# Ringer.net
KiCad netlist of a schematic drawn in EAGLE
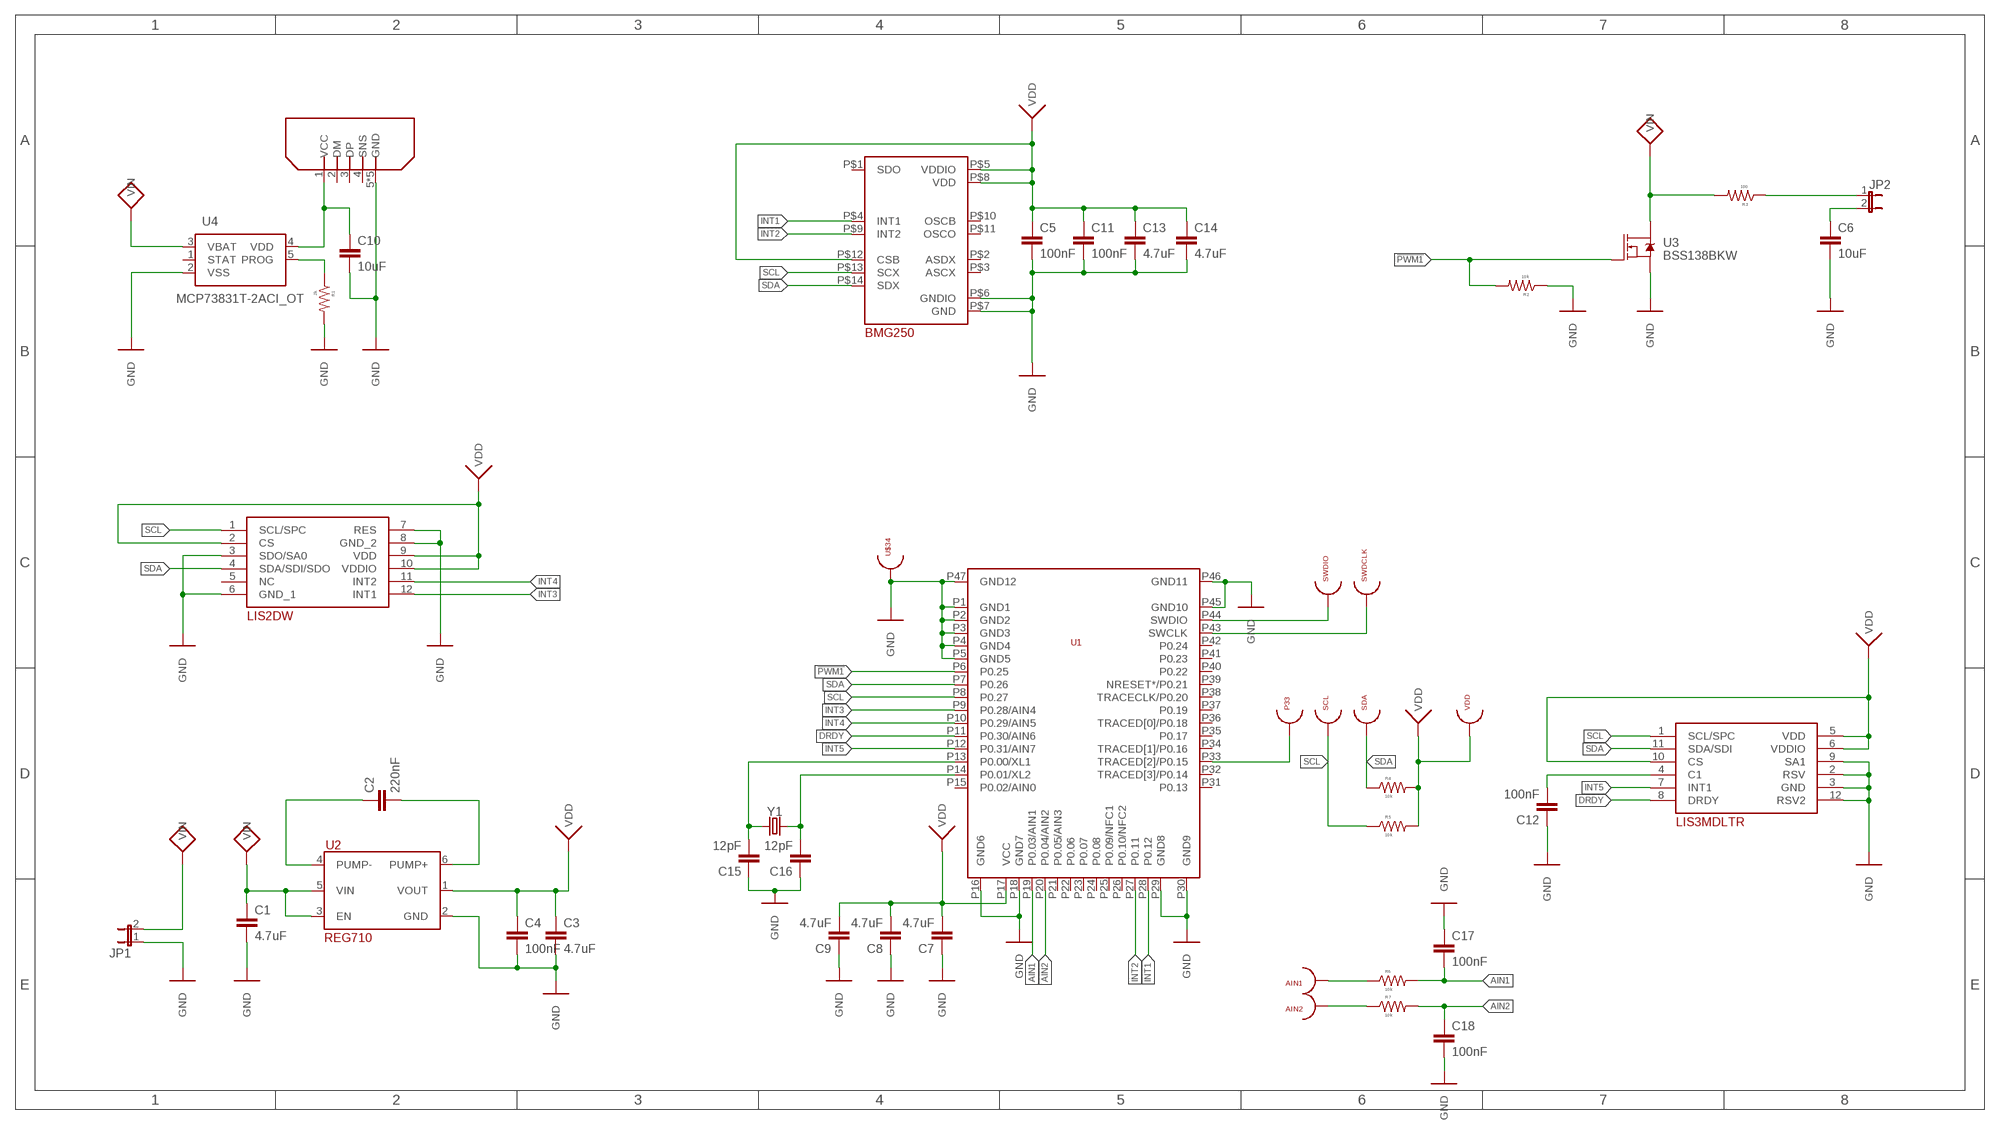
[diagram p0: schematic, sheet 1]

(export (version "E")
  (design (tool "Eeschema 10.0.6"))
  (components
    (comp (ref "AIN1")
      (value "TESTPOINT_22")
      (footprint "eagle-import:TESTPOINT_22")
      (libsource (lib "eagle-import") (part "TESTPOINT_22"))
    )
    (comp (ref "AIN2")
      (value "TESTPOINT_22")
      (footprint "eagle-import:TESTPOINT_22")
      (libsource (lib "eagle-import") (part "TESTPOINT_22"))
    )
    (comp (ref "C1")
      (value "4.7uF")
      (footprint "eagle-import:C0603")
      (libsource (lib "eagle-import") (part "CAPACITOR0603"))
    )
    (comp (ref "C2")
      (value "220nF")
      (footprint "eagle-import:C0603")
      (libsource (lib "eagle-import") (part "CAPACITOR0603"))
    )
    (comp (ref "C3")
      (value "4.7uF")
      (footprint "eagle-import:C0603")
      (libsource (lib "eagle-import") (part "CAPACITOR0603"))
    )
    (comp (ref "C4")
      (value "100nF")
      (footprint "eagle-import:C0603")
      (libsource (lib "eagle-import") (part "CAPACITOR0603"))
    )
    (comp (ref "C5")
      (value "100nF")
      (footprint "eagle-import:C0603")
      (libsource (lib "eagle-import") (part "CAPACITOR0603"))
    )
    (comp (ref "C6")
      (value "10uF")
      (footprint "eagle-import:C0805")
      (libsource (lib "eagle-import") (part "CAPACITOR0805"))
    )
    (comp (ref "C7")
      (value "4.7uF")
      (footprint "eagle-import:C0603")
      (libsource (lib "eagle-import") (part "CAPACITOR0603"))
    )
    (comp (ref "C8")
      (value "4.7uF")
      (footprint "eagle-import:C0603")
      (libsource (lib "eagle-import") (part "CAPACITOR0603"))
    )
    (comp (ref "C9")
      (value "4.7uF")
      (footprint "eagle-import:C0603")
      (libsource (lib "eagle-import") (part "CAPACITOR0603"))
    )
    (comp (ref "C10")
      (value "10uF")
      (footprint "eagle-import:C0603")
      (libsource (lib "eagle-import") (part "CAPACITOR0603"))
    )
    (comp (ref "C11")
      (value "100nF")
      (footprint "eagle-import:C0603")
      (libsource (lib "eagle-import") (part "CAPACITOR0603"))
    )
    (comp (ref "C12")
      (value "100nF")
      (footprint "eagle-import:C0603")
      (libsource (lib "eagle-import") (part "CAPACITOR0603"))
    )
    (comp (ref "C13")
      (value "4.7uF")
      (footprint "eagle-import:C0603")
      (libsource (lib "eagle-import") (part "CAPACITOR0603"))
    )
    (comp (ref "C14")
      (value "4.7uF")
      (footprint "eagle-import:C0603")
      (libsource (lib "eagle-import") (part "CAPACITOR0603"))
    )
    (comp (ref "C15")
      (value "12pF")
      (footprint "eagle-import:C0603")
      (libsource (lib "eagle-import") (part "CAPACITOR0603"))
    )
    (comp (ref "C16")
      (value "12pF")
      (footprint "eagle-import:C0603")
      (libsource (lib "eagle-import") (part "CAPACITOR0603"))
    )
    (comp (ref "C17")
      (value "100nF")
      (footprint "eagle-import:C0603")
      (libsource (lib "eagle-import") (part "CAPACITOR0603"))
    )
    (comp (ref "C18")
      (value "100nF")
      (footprint "eagle-import:C0603")
      (libsource (lib "eagle-import") (part "CAPACITOR0603"))
    )
    (comp (ref "IC1")
      (value "LIS2DW12TR")
      (footprint "eagle-import:LGA-12")
      (fields (field (name "MOUSER_PART_NUMBER") "511-LIS2DW12TR"))
      (libsource (lib "eagle-import") (part "LIS2DW12TR"))
    )
    (comp (ref "JP1")
      (value "JP1E")
      (footprint "eagle-import:JP1")
      (libsource (lib "eagle-import") (part "JP1E"))
    )
    (comp (ref "JP2")
      (value "JP1E")
      (footprint "eagle-import:JP1")
      (libsource (lib "eagle-import") (part "JP1E"))
    )
    (comp (ref "P33")
      (value "TESTPOINT_22")
      (footprint "eagle-import:TESTPOINT_22")
      (libsource (lib "eagle-import") (part "TESTPOINT_22"))
    )
    (comp (ref "R1")
      (value "2k")
      (footprint "eagle-import:R0603")
      (libsource (lib "eagle-import") (part "RESISTOR0603"))
    )
    (comp (ref "R2")
      (value "10k")
      (footprint "eagle-import:R0603")
      (libsource (lib "eagle-import") (part "RESISTOR0603"))
    )
    (comp (ref "R3")
      (value "100")
      (footprint "eagle-import:R0805")
      (libsource (lib "eagle-import") (part "RESISTOR0805"))
    )
    (comp (ref "R4")
      (value "10k")
      (footprint "eagle-import:R0603")
      (libsource (lib "eagle-import") (part "RESISTOR0603"))
    )
    (comp (ref "R5")
      (value "10k")
      (footprint "eagle-import:R0603")
      (libsource (lib "eagle-import") (part "RESISTOR0603"))
    )
    (comp (ref "R6")
      (value "10k")
      (footprint "eagle-import:R0603")
      (libsource (lib "eagle-import") (part "RESISTOR0603"))
    )
    (comp (ref "R7")
      (value "10k")
      (footprint "eagle-import:R0603")
      (libsource (lib "eagle-import") (part "RESISTOR0603"))
    )
    (comp (ref "SCL")
      (value "TESTPOINT_22")
      (footprint "eagle-import:TESTPOINT_22")
      (libsource (lib "eagle-import") (part "TESTPOINT_22"))
    )
    (comp (ref "SDA")
      (value "TESTPOINT_22")
      (footprint "eagle-import:TESTPOINT_22")
      (libsource (lib "eagle-import") (part "TESTPOINT_22"))
    )
    (comp (ref "SWDCLK")
      (value "TESTPOINT_22")
      (footprint "eagle-import:TESTPOINT_22")
      (libsource (lib "eagle-import") (part "TESTPOINT_22"))
    )
    (comp (ref "SWDIO")
      (value "TESTPOINT_22")
      (footprint "eagle-import:TESTPOINT_22")
      (libsource (lib "eagle-import") (part "TESTPOINT_22"))
    )
    (comp (ref "U$23")
      (value "ZX80B5P")
      (footprint "eagle-import:ZX80B5P")
      (libsource (lib "eagle-import") (part "ZX80B5P"))
    )
    (comp (ref "U$29")
      (value "LIS3MDLTR")
      (footprint "eagle-import:LGA-12")
      (libsource (lib "eagle-import") (part "LIS3MDLTR"))
    )
    (comp (ref "U$34")
      (value "TESTPOINT_22")
      (footprint "eagle-import:TESTPOINT_22")
      (libsource (lib "eagle-import") (part "TESTPOINT_22"))
    )
    (comp (ref "U1")
      (value "BMD-300")
      (footprint "eagle-import:BMD-300")
      (libsource (lib "eagle-import") (part "BMD-300"))
    )
    (comp (ref "U2")
      (value "REG710")
      (footprint "eagle-import:SOT457")
      (libsource (lib "eagle-import") (part "REG710"))
    )
    (comp (ref "U3")
      (value "BSS138BKW")
      (footprint "eagle-import:SOT65P210X110-3N")
      (libsource (lib "eagle-import") (part "BSS138BKW"))
    )
    (comp (ref "U4")
      (value "MCP73831T-2ACI_OT")
      (footprint "eagle-import:SOT95P270X145-5N")
      (fields
        (field (name "MANUFACTURER_PART_NUMBER") "MCP73831T-2ACI/OT")
        (field (name "MOUSER_PART_NUMBER") "579-MCP73831T-2ACIOT")
      )
      (libsource (lib "eagle-import") (part "MCP73831T-2ACI_OT"))
    )
    (comp (ref "U5")
      (value "BMG250")
      (footprint "eagle-import:LGA14")
      (libsource (lib "eagle-import") (part "BMG250"))
    )
    (comp (ref "VDD")
      (value "TESTPOINT_22")
      (footprint "eagle-import:TESTPOINT_22")
      (libsource (lib "eagle-import") (part "TESTPOINT_22"))
    )
    (comp (ref "Y1")
      (value "CRYSTALSMD-3.2X1.5")
      (footprint "eagle-import:CRYSTAL-SMD-3.2X1.5MM")
      (libsource (lib "eagle-import") (part "CRYSTALSMD-3.2X1.5"))
    )
  )
  (nets
    (net (code "1") (name "/~{PWM1}") (class "Default")
      (node (ref "R2") (pin "2") (pinfunction "2_2") (pintype "passive"))
      (node (ref "U1") (pin "P6") (pinfunction "P0.25_P6") (pintype "bidirectional"))
      (node (ref "U3") (pin "1") (pinfunction "G_1") (pintype "bidirectional"))
    )
    (net (code "2") (name "AIN1") (class "Default")
      (node (ref "C17") (pin "2") (pinfunction "2_2") (pintype "passive"))
      (node (ref "R6") (pin "2") (pinfunction "2_2") (pintype "passive"))
      (node (ref "U1") (pin "P19") (pinfunction "P0.03/AIN1_P19") (pintype "bidirectional"))
    )
    (net (code "3") (name "AIN2") (class "Default")
      (node (ref "C18") (pin "1") (pinfunction "1_1") (pintype "passive"))
      (node (ref "R7") (pin "2") (pinfunction "2_2") (pintype "passive"))
      (node (ref "U1") (pin "P20") (pinfunction "P0.04/AIN2_P20") (pintype "bidirectional"))
    )
    (net (code "4") (name "DRDY") (class "Default")
      (node (ref "U$29") (pin "8") (pinfunction "DRDY_8") (pintype "bidirectional"))
      (node (ref "U1") (pin "P11") (pinfunction "P0.30/AIN6_P11") (pintype "bidirectional"))
    )
    (net (code "5") (name "GND") (class "Default")
      (node (ref "C1") (pin "2") (pinfunction "2_2") (pintype "passive"))
      (node (ref "C10") (pin "2") (pinfunction "2_2") (pintype "passive"))
      (node (ref "C11") (pin "2") (pinfunction "2_2") (pintype "passive"))
      (node (ref "C12") (pin "1") (pinfunction "1_1") (pintype "passive"))
      (node (ref "C13") (pin "2") (pinfunction "2_2") (pintype "passive"))
      (node (ref "C14") (pin "2") (pinfunction "2_2") (pintype "passive"))
      (node (ref "C15") (pin "1") (pinfunction "1_1") (pintype "passive"))
      (node (ref "C16") (pin "1") (pinfunction "1_1") (pintype "passive"))
      (node (ref "C17") (pin "1") (pinfunction "1_1") (pintype "passive"))
      (node (ref "C18") (pin "2") (pinfunction "2_2") (pintype "passive"))
      (node (ref "C3") (pin "2") (pinfunction "2_2") (pintype "passive"))
      (node (ref "C4") (pin "2") (pinfunction "2_2") (pintype "passive"))
      (node (ref "C5") (pin "2") (pinfunction "2_2") (pintype "passive"))
      (node (ref "C6") (pin "2") (pinfunction "2_2") (pintype "passive"))
      (node (ref "C7") (pin "1") (pinfunction "1_1") (pintype "passive"))
      (node (ref "C8") (pin "1") (pinfunction "1_1") (pintype "passive"))
      (node (ref "C9") (pin "1") (pinfunction "1_1") (pintype "passive"))
      (node (ref "IC1") (pin "3") (pinfunction "SDO/SA0_3") (pintype "bidirectional"))
      (node (ref "IC1") (pin "6") (pinfunction "GND_1_6") (pintype "bidirectional"))
      (node (ref "IC1") (pin "7") (pinfunction "RES_7") (pintype "bidirectional"))
      (node (ref "IC1") (pin "8") (pinfunction "GND_2_8") (pintype "bidirectional"))
      (node (ref "JP1") (pin "1") (pinfunction "1_1") (pintype "passive"))
      (node (ref "R1") (pin "2") (pinfunction "2_2") (pintype "passive"))
      (node (ref "R2") (pin "1") (pinfunction "1_1") (pintype "passive"))
      (node (ref "U$23") (pin "5") (pinfunction "GND_5") (pintype "bidirectional"))
      (node (ref "U$23") (pin "GND1") (pinfunction "GND_GND1") (pintype "bidirectional"))
      (node (ref "U$23") (pin "GND2") (pinfunction "GND_GND2") (pintype "bidirectional"))
      (node (ref "U$23") (pin "GND3") (pinfunction "GND_GND3") (pintype "bidirectional"))
      (node (ref "U$23") (pin "GND4") (pinfunction "GND_GND4") (pintype "bidirectional"))
      (node (ref "U$29") (pin "12") (pinfunction "RSV2_12") (pintype "bidirectional"))
      (node (ref "U$29") (pin "2") (pinfunction "RSV_2") (pintype "bidirectional"))
      (node (ref "U$29") (pin "3") (pinfunction "GND_3") (pintype "bidirectional"))
      (node (ref "U$29") (pin "9") (pinfunction "SA1_9") (pintype "bidirectional"))
      (node (ref "U$34") (pin "P$1") (pinfunction "P$1_P$1") (pintype "bidirectional"))
      (node (ref "U1") (pin "P1") (pinfunction "GND1_P1") (pintype "bidirectional"))
      (node (ref "U1") (pin "P16") (pinfunction "GND6_P16") (pintype "bidirectional"))
      (node (ref "U1") (pin "P18") (pinfunction "GND7_P18") (pintype "bidirectional"))
      (node (ref "U1") (pin "P2") (pinfunction "GND2_P2") (pintype "bidirectional"))
      (node (ref "U1") (pin "P29") (pinfunction "GND8_P29") (pintype "bidirectional"))
      (node (ref "U1") (pin "P3") (pinfunction "GND3_P3") (pintype "bidirectional"))
      (node (ref "U1") (pin "P30") (pinfunction "GND9_P30") (pintype "bidirectional"))
      (node (ref "U1") (pin "P4") (pinfunction "GND4_P4") (pintype "bidirectional"))
      (node (ref "U1") (pin "P45") (pinfunction "GND10_P45") (pintype "bidirectional"))
      (node (ref "U1") (pin "P46") (pinfunction "GND11_P46") (pintype "bidirectional"))
      (node (ref "U1") (pin "P47") (pinfunction "GND12_P47") (pintype "bidirectional"))
      (node (ref "U1") (pin "P5") (pinfunction "GND5_P5") (pintype "bidirectional"))
      (node (ref "U2") (pin "2") (pinfunction "GND_2") (pintype "bidirectional"))
      (node (ref "U3") (pin "2") (pinfunction "S_2") (pintype "bidirectional"))
      (node (ref "U4") (pin "2") (pinfunction "VSS_2") (pintype "bidirectional"))
      (node (ref "U5") (pin "P$6") (pinfunction "GNDIO_P$6") (pintype "power_in"))
      (node (ref "U5") (pin "P$7") (pinfunction "GND_P$7") (pintype "power_in"))
    )
    (net (code "6") (name "INT1") (class "Default")
      (node (ref "U1") (pin "P28") (pinfunction "P0.12_P28") (pintype "bidirectional"))
      (node (ref "U5") (pin "P$4") (pinfunction "INT1_P$4") (pintype "bidirectional"))
    )
    (net (code "7") (name "INT2") (class "Default")
      (node (ref "U1") (pin "P27") (pinfunction "P0.11_P27") (pintype "bidirectional"))
      (node (ref "U5") (pin "P$9") (pinfunction "INT2_P$9") (pintype "bidirectional"))
    )
    (net (code "8") (name "INT3") (class "Default")
      (node (ref "IC1") (pin "12") (pinfunction "INT1_12") (pintype "bidirectional"))
      (node (ref "U1") (pin "P9") (pinfunction "P0.28/AIN4_P9") (pintype "bidirectional"))
    )
    (net (code "9") (name "INT4") (class "Default")
      (node (ref "IC1") (pin "11") (pinfunction "INT2_11") (pintype "bidirectional"))
      (node (ref "U1") (pin "P10") (pinfunction "P0.29/AIN5_P10") (pintype "bidirectional"))
    )
    (net (code "10") (name "INT5") (class "Default")
      (node (ref "U$29") (pin "7") (pinfunction "INT1_7") (pintype "bidirectional"))
      (node (ref "U1") (pin "P12") (pinfunction "P0.31/AIN7_P12") (pintype "bidirectional"))
    )
    (net (code "11") (name "Net-(AIN1-PadP$1)") (class "Default")
      (node (ref "AIN1") (pin "P$1") (pinfunction "P$1_P$1") (pintype "bidirectional"))
      (node (ref "R6") (pin "1") (pinfunction "1_1") (pintype "passive"))
    )
    (net (code "12") (name "Net-(AIN2-PadP$1)") (class "Default")
      (node (ref "AIN2") (pin "P$1") (pinfunction "P$1_P$1") (pintype "bidirectional"))
      (node (ref "R7") (pin "1") (pinfunction "1_1") (pintype "passive"))
    )
    (net (code "13") (name "Net-(C6-Pad1)") (class "Default")
      (node (ref "C6") (pin "1") (pinfunction "1_1") (pintype "passive"))
      (node (ref "JP2") (pin "2") (pinfunction "2_2") (pintype "passive"))
    )
    (net (code "14") (name "Net-(JP2-Pad1)") (class "Default")
      (node (ref "JP2") (pin "1") (pinfunction "1_1") (pintype "passive"))
      (node (ref "R3") (pin "1") (pinfunction "1_1") (pintype "passive"))
    )
    (net (code "15") (name "Net-(U$23-VCC)") (class "Default")
      (node (ref "C10") (pin "1") (pinfunction "1_1") (pintype "passive"))
      (node (ref "U$23") (pin "1") (pinfunction "VCC_1") (pintype "bidirectional"))
      (node (ref "U4") (pin "4") (pinfunction "VDD_4") (pintype "bidirectional"))
    )
    (net (code "16") (name "Net-(U$29-C1)") (class "Default")
      (node (ref "C12") (pin "2") (pinfunction "2_2") (pintype "passive"))
      (node (ref "U$29") (pin "4") (pinfunction "C1_4") (pintype "bidirectional"))
    )
    (net (code "17") (name "Net-(U1-P0.00{slash}XL1)") (class "Default")
      (node (ref "C15") (pin "2") (pinfunction "2_2") (pintype "passive"))
      (node (ref "U1") (pin "P13") (pinfunction "P0.00/XL1_P13") (pintype "bidirectional"))
      (node (ref "Y1") (pin "P$1") (pinfunction "1_P$1") (pintype "passive"))
    )
    (net (code "18") (name "Net-(U1-P0.01{slash}XL2)") (class "Default")
      (node (ref "C16") (pin "2") (pinfunction "2_2") (pintype "passive"))
      (node (ref "U1") (pin "P14") (pinfunction "P0.01/XL2_P14") (pintype "bidirectional"))
      (node (ref "Y1") (pin "P$2") (pinfunction "2_P$2") (pintype "passive"))
    )
    (net (code "19") (name "Net-(U1-SWCLK)") (class "Default")
      (node (ref "SWDCLK") (pin "P$1") (pinfunction "P$1_P$1") (pintype "bidirectional"))
      (node (ref "U1") (pin "P43") (pinfunction "SWCLK_P43") (pintype "bidirectional"))
    )
    (net (code "20") (name "Net-(U1-SWDIO)") (class "Default")
      (node (ref "SWDIO") (pin "P$1") (pinfunction "P$1_P$1") (pintype "bidirectional"))
      (node (ref "U1") (pin "P44") (pinfunction "SWDIO_P44") (pintype "bidirectional"))
    )
    (net (code "21") (name "Net-(U1-TRACED[2]{slash}P0.15)") (class "Default")
      (node (ref "P33") (pin "P$1") (pinfunction "P$1_P$1") (pintype "bidirectional"))
      (node (ref "U1") (pin "P33") (pinfunction "TRACED[2]/P0.15_P33") (pintype "bidirectional"))
    )
    (net (code "22") (name "Net-(U2-PUMP+)") (class "Default")
      (node (ref "C2") (pin "2") (pinfunction "2_2") (pintype "passive"))
      (node (ref "U2") (pin "6") (pinfunction "PUMP+_6") (pintype "bidirectional"))
    )
    (net (code "23") (name "Net-(U2-PUMP-)") (class "Default")
      (node (ref "C2") (pin "1") (pinfunction "1_1") (pintype "passive"))
      (node (ref "U2") (pin "4") (pinfunction "PUMP-_4") (pintype "bidirectional"))
    )
    (net (code "24") (name "Net-(U4-PROG)") (class "Default")
      (node (ref "R1") (pin "1") (pinfunction "1_1") (pintype "passive"))
      (node (ref "U4") (pin "5") (pinfunction "PROG_5") (pintype "bidirectional"))
    )
    (net (code "25") (name "SCL") (class "Default")
      (node (ref "IC1") (pin "1") (pinfunction "SCL/SPC_1") (pintype "bidirectional"))
      (node (ref "R5") (pin "1") (pinfunction "1_1") (pintype "passive"))
      (node (ref "SCL") (pin "P$1") (pinfunction "P$1_P$1") (pintype "bidirectional"))
      (node (ref "U$29") (pin "1") (pinfunction "SCL/SPC_1") (pintype "bidirectional"))
      (node (ref "U1") (pin "P8") (pinfunction "P0.27_P8") (pintype "bidirectional"))
      (node (ref "U5") (pin "P$13") (pinfunction "SCX_P$13") (pintype "bidirectional"))
    )
    (net (code "26") (name "SDA") (class "Default")
      (node (ref "IC1") (pin "4") (pinfunction "SDA/SDI/SDO_4") (pintype "bidirectional"))
      (node (ref "R4") (pin "1") (pinfunction "1_1") (pintype "passive"))
      (node (ref "SDA") (pin "P$1") (pinfunction "P$1_P$1") (pintype "bidirectional"))
      (node (ref "U$29") (pin "11") (pinfunction "SDA/SDI_11") (pintype "bidirectional"))
      (node (ref "U1") (pin "P7") (pinfunction "P0.26_P7") (pintype "bidirectional"))
      (node (ref "U5") (pin "P$14") (pinfunction "SDX_P$14") (pintype "bidirectional"))
    )
    (net (code "27") (name "VDD") (class "Default")
      (node (ref "C11") (pin "1") (pinfunction "1_1") (pintype "passive"))
      (node (ref "C13") (pin "1") (pinfunction "1_1") (pintype "passive"))
      (node (ref "C14") (pin "1") (pinfunction "1_1") (pintype "passive"))
      (node (ref "C3") (pin "1") (pinfunction "1_1") (pintype "passive"))
      (node (ref "C4") (pin "1") (pinfunction "1_1") (pintype "passive"))
      (node (ref "C5") (pin "1") (pinfunction "1_1") (pintype "passive"))
      (node (ref "C7") (pin "2") (pinfunction "2_2") (pintype "passive"))
      (node (ref "C8") (pin "2") (pinfunction "2_2") (pintype "passive"))
      (node (ref "C9") (pin "2") (pinfunction "2_2") (pintype "passive"))
      (node (ref "IC1") (pin "10") (pinfunction "VDDIO_10") (pintype "bidirectional"))
      (node (ref "IC1") (pin "2") (pinfunction "CS_2") (pintype "bidirectional"))
      (node (ref "IC1") (pin "9") (pinfunction "VDD_9") (pintype "bidirectional"))
      (node (ref "R4") (pin "2") (pinfunction "2_2") (pintype "passive"))
      (node (ref "R5") (pin "2") (pinfunction "2_2") (pintype "passive"))
      (node (ref "U$29") (pin "10") (pinfunction "CS_10") (pintype "bidirectional"))
      (node (ref "U$29") (pin "5") (pinfunction "VDD_5") (pintype "bidirectional"))
      (node (ref "U$29") (pin "6") (pinfunction "VDDIO_6") (pintype "bidirectional"))
      (node (ref "U1") (pin "P17") (pinfunction "VCC_P17") (pintype "bidirectional"))
      (node (ref "U2") (pin "1") (pinfunction "VOUT_1") (pintype "bidirectional"))
      (node (ref "U5") (pin "P$12") (pinfunction "CSB_P$12") (pintype "bidirectional"))
      (node (ref "U5") (pin "P$5") (pinfunction "VDDIO_P$5") (pintype "power_in"))
      (node (ref "U5") (pin "P$8") (pinfunction "VDD_P$8") (pintype "power_in"))
      (node (ref "VDD") (pin "P$1") (pinfunction "P$1_P$1") (pintype "bidirectional"))
    )
    (net (code "28") (name "VIN") (class "Default")
      (node (ref "C1") (pin "1") (pinfunction "1_1") (pintype "passive"))
      (node (ref "JP1") (pin "2") (pinfunction "2_2") (pintype "passive"))
      (node (ref "R3") (pin "2") (pinfunction "2_2") (pintype "passive"))
      (node (ref "U2") (pin "3") (pinfunction "EN_3") (pintype "bidirectional"))
      (node (ref "U2") (pin "5") (pinfunction "VIN_5") (pintype "bidirectional"))
      (node (ref "U3") (pin "3") (pinfunction "D_3") (pintype "bidirectional"))
      (node (ref "U4") (pin "3") (pinfunction "VBAT_3") (pintype "bidirectional"))
    )
    (net (code "29") (name "unconnected-(IC1-NC-Pad5)") (class "Default")
      (node (ref "IC1") (pin "5") (pinfunction "NC_5") (pintype "no_connect"))
    )
    (net (code "30") (name "unconnected-(U$23-DM-Pad2)") (class "Default")
      (node (ref "U$23") (pin "2") (pinfunction "DM_2") (pintype "bidirectional"))
    )
    (net (code "31") (name "unconnected-(U$23-DP-Pad3)") (class "Default")
      (node (ref "U$23") (pin "3") (pinfunction "DP_3") (pintype "bidirectional"))
    )
    (net (code "32") (name "unconnected-(U$23-SNS-Pad4)") (class "Default")
      (node (ref "U$23") (pin "4") (pinfunction "SNS_4") (pintype "bidirectional"))
    )
    (net (code "33") (name "unconnected-(U1-NRESET*{slash}P0.21-PadP39)") (class "Default")
      (node (ref "U1") (pin "P39") (pinfunction "NRESET*/P0.21_P39") (pintype "bidirectional"))
    )
    (net (code "34") (name "unconnected-(U1-P0.02{slash}AIN0-PadP15)") (class "Default")
      (node (ref "U1") (pin "P15") (pinfunction "P0.02/AIN0_P15") (pintype "bidirectional"))
    )
    (net (code "35") (name "unconnected-(U1-P0.05{slash}AIN3-PadP21)") (class "Default")
      (node (ref "U1") (pin "P21") (pinfunction "P0.05/AIN3_P21") (pintype "bidirectional"))
    )
    (net (code "36") (name "unconnected-(U1-P0.06-PadP22)") (class "Default")
      (node (ref "U1") (pin "P22") (pinfunction "P0.06_P22") (pintype "bidirectional"))
    )
    (net (code "37") (name "unconnected-(U1-P0.07-PadP23)") (class "Default")
      (node (ref "U1") (pin "P23") (pinfunction "P0.07_P23") (pintype "bidirectional"))
    )
    (net (code "38") (name "unconnected-(U1-P0.08-PadP24)") (class "Default")
      (node (ref "U1") (pin "P24") (pinfunction "P0.08_P24") (pintype "bidirectional"))
    )
    (net (code "39") (name "unconnected-(U1-P0.09{slash}NFC1-PadP25)") (class "Default")
      (node (ref "U1") (pin "P25") (pinfunction "P0.09/NFC1_P25") (pintype "bidirectional"))
    )
    (net (code "40") (name "unconnected-(U1-P0.10{slash}NFC2-PadP26)") (class "Default")
      (node (ref "U1") (pin "P26") (pinfunction "P0.10/NFC2_P26") (pintype "bidirectional"))
    )
    (net (code "41") (name "unconnected-(U1-P0.13-PadP31)") (class "Default")
      (node (ref "U1") (pin "P31") (pinfunction "P0.13_P31") (pintype "bidirectional"))
    )
    (net (code "42") (name "unconnected-(U1-P0.17-PadP35)") (class "Default")
      (node (ref "U1") (pin "P35") (pinfunction "P0.17_P35") (pintype "bidirectional"))
    )
    (net (code "43") (name "unconnected-(U1-P0.19-PadP37)") (class "Default")
      (node (ref "U1") (pin "P37") (pinfunction "P0.19_P37") (pintype "bidirectional"))
    )
    (net (code "44") (name "unconnected-(U1-P0.22-PadP40)") (class "Default")
      (node (ref "U1") (pin "P40") (pinfunction "P0.22_P40") (pintype "bidirectional"))
    )
    (net (code "45") (name "unconnected-(U1-P0.23-PadP41)") (class "Default")
      (node (ref "U1") (pin "P41") (pinfunction "P0.23_P41") (pintype "bidirectional"))
    )
    (net (code "46") (name "unconnected-(U1-P0.24-PadP42)") (class "Default")
      (node (ref "U1") (pin "P42") (pinfunction "P0.24_P42") (pintype "bidirectional"))
    )
    (net (code "47") (name "unconnected-(U1-TRACECLK{slash}P0.20-PadP38)") (class "Default")
      (node (ref "U1") (pin "P38") (pinfunction "TRACECLK/P0.20_P38") (pintype "bidirectional"))
    )
    (net (code "48") (name "unconnected-(U1-TRACED[0]{slash}P0.18-PadP36)") (class "Default")
      (node (ref "U1") (pin "P36") (pinfunction "TRACED[0]/P0.18_P36") (pintype "bidirectional"))
    )
    (net (code "49") (name "unconnected-(U1-TRACED[1]{slash}P0.16-PadP34)") (class "Default")
      (node (ref "U1") (pin "P34") (pinfunction "TRACED[1]/P0.16_P34") (pintype "bidirectional"))
    )
    (net (code "50") (name "unconnected-(U1-TRACED[3]{slash}P0.14-PadP32)") (class "Default")
      (node (ref "U1") (pin "P32") (pinfunction "TRACED[3]/P0.14_P32") (pintype "bidirectional"))
    )
    (net (code "51") (name "unconnected-(U4-STAT-Pad1)") (class "Default")
      (node (ref "U4") (pin "1") (pinfunction "STAT_1") (pintype "bidirectional"))
    )
    (net (code "52") (name "unconnected-(U5-ASCX-PadP$3)") (class "Default")
      (node (ref "U5") (pin "P$3") (pinfunction "ASCX_P$3") (pintype "bidirectional"))
    )
    (net (code "53") (name "unconnected-(U5-ASDX-PadP$2)") (class "Default")
      (node (ref "U5") (pin "P$2") (pinfunction "ASDX_P$2") (pintype "bidirectional"))
    )
    (net (code "54") (name "unconnected-(U5-OSCB-PadP$10)") (class "Default")
      (node (ref "U5") (pin "P$10") (pinfunction "OSCB_P$10") (pintype "bidirectional"))
    )
    (net (code "55") (name "unconnected-(U5-OSCO-PadP$11)") (class "Default")
      (node (ref "U5") (pin "P$11") (pinfunction "OSCO_P$11") (pintype "bidirectional"))
    )
    (net (code "56") (name "unconnected-(U5-SDO-PadP$1)") (class "Default")
      (node (ref "U5") (pin "P$1") (pinfunction "SDO_P$1") (pintype "bidirectional"))
    )
  )
)
